# design.net
KiCad netlist of a schematic drawn in Altium Designer
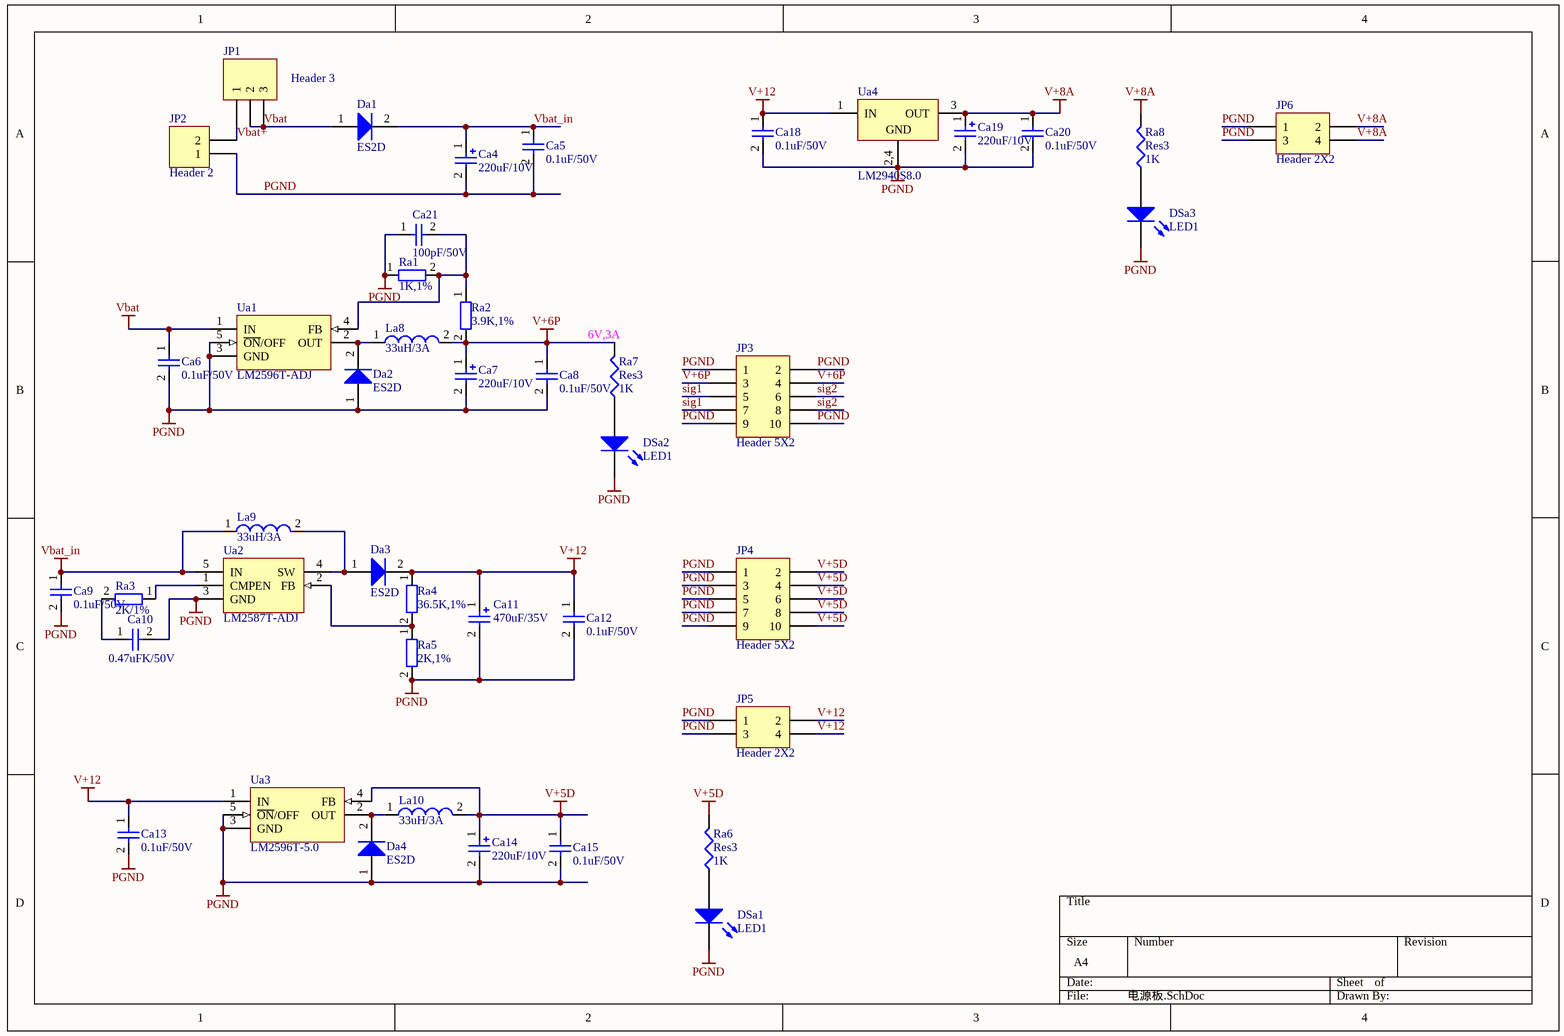
[diagram p0: 电源板.SchDoc]

(export (version "E")
  (design (tool "Eeschema 10.0.6"))
  (components
    (comp (ref "Ca4")
      (value "220uF/10V")
      (footprint "470U")
      (description "Polarized Capacitor (Radial)")
      (fields
        (field (name "MANUFACTURER") "Generic Components")
        (field (name "Comment") "Cap Pol1")
        (field (name "PUBLISHER") "Altium Hobart Technology Centre")
      )
      (libsource (lib "YX002") (part "Cap Pol1"))
    )
    (comp (ref "Ca5")
      (value "0.1uF/50V")
      (footprint "CR2012-0805")
      (description "Capacitor")
      (fields
        (field (name "MANUFACTURER") "Generic Components")
        (field (name "Comment") "Cap")
        (field (name "PUBLISHER") "Altium Hobart Technology Centre")
      )
      (libsource (lib "YX002") (part "Cap"))
    )
    (comp (ref "Ca6")
      (value "0.1uF/50V")
      (footprint "CR2012-0805")
      (description "Capacitor")
      (fields
        (field (name "MANUFACTURER") "Generic Components")
        (field (name "Comment") "Cap")
        (field (name "PUBLISHER") "Altium Hobart Technology Centre")
      )
      (libsource (lib "YX002") (part "Cap"))
    )
    (comp (ref "Ca7")
      (value "220uF/10V")
      (footprint "470U")
      (description "Polarized Capacitor (Radial)")
      (fields
        (field (name "MANUFACTURER") "Generic Components")
        (field (name "Comment") "Cap Pol1")
        (field (name "PUBLISHER") "Altium Hobart Technology Centre")
      )
      (libsource (lib "YX002") (part "Cap Pol1"))
    )
    (comp (ref "Ca8")
      (value "0.1uF/50V")
      (footprint "CR2012-0805")
      (description "Capacitor")
      (fields
        (field (name "MANUFACTURER") "Generic Components")
        (field (name "Comment") "Cap")
        (field (name "PUBLISHER") "Altium Hobart Technology Centre")
      )
      (libsource (lib "YX002") (part "Cap"))
    )
    (comp (ref "Ca9")
      (value "0.1uF/50V")
      (footprint "CR2012-0805")
      (description "Capacitor")
      (fields
        (field (name "MANUFACTURER") "Generic Components")
        (field (name "Comment") "Cap")
        (field (name "PUBLISHER") "Altium Hobart Technology Centre")
      )
      (libsource (lib "YX002") (part "Cap"))
    )
    (comp (ref "Ca10")
      (value "0.47uFK/50V")
      (footprint "CR2012-0805")
      (description "Capacitor")
      (fields
        (field (name "MANUFACTURER") "Generic Components")
        (field (name "Comment") "Cap")
        (field (name "PUBLISHER") "Altium Hobart Technology Centre")
      )
      (libsource (lib "YX002") (part "Cap"))
    )
    (comp (ref "Ca11")
      (value "470uF/35V")
      (footprint "470U")
      (description "Polarized Capacitor (Radial)")
      (fields
        (field (name "MANUFACTURER") "Generic Components")
        (field (name "Comment") "Cap Pol1")
        (field (name "PUBLISHER") "Altium Hobart Technology Centre")
      )
      (libsource (lib "YX002") (part "Cap Pol1"))
    )
    (comp (ref "Ca12")
      (value "0.1uF/50V")
      (footprint "CR2012-0805")
      (description "Capacitor")
      (fields
        (field (name "MANUFACTURER") "Generic Components")
        (field (name "Comment") "Cap")
        (field (name "PUBLISHER") "Altium Hobart Technology Centre")
      )
      (libsource (lib "YX002") (part "Cap"))
    )
    (comp (ref "Ca13")
      (value "0.1uF/50V")
      (footprint "CR2012-0805")
      (description "Capacitor")
      (fields
        (field (name "MANUFACTURER") "Generic Components")
        (field (name "Comment") "Cap")
        (field (name "PUBLISHER") "Altium Hobart Technology Centre")
      )
      (libsource (lib "YX002") (part "Cap"))
    )
    (comp (ref "Ca14")
      (value "220uF/10V")
      (footprint "100u")
      (description "Polarized Capacitor (Radial)")
      (fields
        (field (name "MANUFACTURER") "Generic Components")
        (field (name "Comment") "Cap Pol1")
        (field (name "PUBLISHER") "Altium Hobart Technology Centre")
      )
      (libsource (lib "YX002") (part "Cap Pol1"))
    )
    (comp (ref "Ca15")
      (value "0.1uF/50V")
      (footprint "CR2012-0805")
      (description "Capacitor")
      (fields
        (field (name "MANUFACTURER") "Generic Components")
        (field (name "Comment") "Cap")
        (field (name "PUBLISHER") "Altium Hobart Technology Centre")
      )
      (libsource (lib "YX002") (part "Cap"))
    )
    (comp (ref "Ca18")
      (value "0.1uF/50V")
      (footprint "CR2012-0805")
      (description "Capacitor")
      (fields
        (field (name "MANUFACTURER") "Generic Components")
        (field (name "Comment") "Cap")
        (field (name "PUBLISHER") "Altium Hobart Technology Centre")
      )
      (libsource (lib "YX002") (part "Cap"))
    )
    (comp (ref "Ca19")
      (value "220uF/10V")
      (footprint "100u")
      (description "Polarized Capacitor (Radial)")
      (fields
        (field (name "MANUFACTURER") "Generic Components")
        (field (name "Comment") "Cap Pol1")
        (field (name "PUBLISHER") "Altium Hobart Technology Centre")
      )
      (libsource (lib "YX002") (part "Cap Pol1"))
    )
    (comp (ref "Ca20")
      (value "0.1uF/50V")
      (footprint "CR2012-0805")
      (description "Capacitor")
      (fields
        (field (name "MANUFACTURER") "Generic Components")
        (field (name "Comment") "Cap")
        (field (name "PUBLISHER") "Altium Hobart Technology Centre")
      )
      (libsource (lib "YX002") (part "Cap"))
    )
    (comp (ref "Ca21")
      (value "100pF/50V")
      (footprint "CR2012-0805")
      (description "Capacitor")
      (fields
        (field (name "MANUFACTURER") "Generic Components")
        (field (name "Comment") "Cap")
        (field (name "PUBLISHER") "Altium Hobart Technology Centre")
      )
      (libsource (lib "YX002") (part "Cap"))
    )
    (comp (ref "Da1")
      (value "ES2D")
      (footprint "DO-214-SMB-YX1")
      (description "Ultra-Fast Rectifier Diode")
      (fields
        (field (name "MANUFACTURER") "Generic Components")
        (field (name "Comment") "Diode_UFR")
        (field (name "PUBLISHER") "Altium Hobart Technology Centre")
      )
      (libsource (lib "YX002") (part "Diode_UFR"))
    )
    (comp (ref "Da2")
      (value "ES2D")
      (footprint "DO-214-SMB-YX1")
      (description "Ultra-Fast Rectifier Diode")
      (fields
        (field (name "MANUFACTURER") "Generic Components")
        (field (name "Comment") "Diode_UFR")
        (field (name "PUBLISHER") "Altium Hobart Technology Centre")
      )
      (libsource (lib "YX002") (part "Diode_UFR"))
    )
    (comp (ref "Da3")
      (value "ES2D")
      (footprint "DO-214-SMB-YX1")
      (description "Ultra-Fast Rectifier Diode")
      (fields
        (field (name "MANUFACTURER") "Generic Components")
        (field (name "Comment") "Diode_UFR")
        (field (name "PUBLISHER") "Altium Hobart Technology Centre")
      )
      (libsource (lib "YX002") (part "Diode_UFR"))
    )
    (comp (ref "Da4")
      (value "ES2D")
      (footprint "DO-214-SMB-YX1")
      (description "Ultra-Fast Rectifier Diode")
      (fields
        (field (name "MANUFACTURER") "Generic Components")
        (field (name "Comment") "Diode_UFR")
        (field (name "PUBLISHER") "Altium Hobart Technology Centre")
      )
      (libsource (lib "YX002") (part "Diode_UFR"))
    )
    (comp (ref "DSa1")
      (value "LED1")
      (footprint "CR2012-0805")
      (description "Typical RED GaAs LED")
      (fields (field (name "PUBLISHER") "Altium Limited"))
      (libsource (lib "Miscellaneous Devices") (part "LED1"))
    )
    (comp (ref "DSa2")
      (value "LED1")
      (footprint "CR2012-0805")
      (description "Typical RED GaAs LED")
      (fields (field (name "PUBLISHER") "Altium Limited"))
      (libsource (lib "Miscellaneous Devices") (part "LED1"))
    )
    (comp (ref "DSa3")
      (value "LED1")
      (footprint "CR2012-0805")
      (description "Typical RED GaAs LED")
      (fields (field (name "PUBLISHER") "Altium Limited"))
      (libsource (lib "Miscellaneous Devices") (part "LED1"))
    )
    (comp (ref "JP1")
      (value "Header 3")
      (footprint "KG_3")
      (description "Header, 3-Pin")
      (fields (field (name "PUBLISHER") "Altium Limited"))
      (libsource (lib "Miscellaneous Connectors") (part "Header 3"))
    )
    (comp (ref "JP2")
      (value "Header 2")
      (footprint "CON_X2_B")
      (description "Header, 2-Pin")
      (fields (field (name "PUBLISHER") "Altium Limited"))
      (libsource (lib "Miscellaneous Connectors") (part "Header 2"))
    )
    (comp (ref "JP3")
      (value "Header 5X2")
      (footprint "HDR2X5")
      (description "Header, 5-Pin, Dual row")
      (fields (field (name "PUBLISHER") "Altium Limited"))
      (libsource (lib "Miscellaneous Connectors") (part "Header 5X2"))
    )
    (comp (ref "JP4")
      (value "Header 5X2")
      (footprint "HDR2X5")
      (description "Header, 5-Pin, Dual row")
      (fields (field (name "PUBLISHER") "Altium Limited"))
      (libsource (lib "Miscellaneous Connectors") (part "Header 5X2"))
    )
    (comp (ref "JP5")
      (value "Header 2X2")
      (footprint "HDR2X2")
      (description "Header, 2-Pin, Dual row")
      (fields (field (name "PUBLISHER") "Altium Limited"))
      (libsource (lib "Miscellaneous Connectors") (part "Header 2X2"))
    )
    (comp (ref "JP6")
      (value "Header 2X2")
      (footprint "HDR2X2")
      (description "Header, 2-Pin, Dual row")
      (fields (field (name "PUBLISHER") "Altium Limited"))
      (libsource (lib "Miscellaneous Connectors") (part "Header 2X2"))
    )
    (comp (ref "La8")
      (value "33uH/3A")
      (footprint "INDUCTOR-YX14")
      (description "Inductor")
      (fields
        (field (name "MANUFACTURER") "Generic Components")
        (field (name "PUBLISHER") "Altium Hobart Technology Centre")
      )
      (libsource (lib "YX002") (part "Inductor"))
    )
    (comp (ref "La9")
      (value "33uH/3A")
      (footprint "INDUCTOR-YX14")
      (description "Inductor")
      (fields
        (field (name "MANUFACTURER") "Generic Components")
        (field (name "PUBLISHER") "Altium Hobart Technology Centre")
      )
      (libsource (lib "YX002") (part "Inductor"))
    )
    (comp (ref "La10")
      (value "33uH/3A")
      (footprint "INDUCTOR-YX14")
      (description "Inductor")
      (fields
        (field (name "MANUFACTURER") "Generic Components")
        (field (name "PUBLISHER") "Altium Hobart Technology Centre")
      )
      (libsource (lib "YX002") (part "Inductor"))
    )
    (comp (ref "Ra1")
      (value "1K,1%")
      (footprint "CR2012-0805")
      (description "Resistor")
      (fields
        (field (name "MANUFACTURER") "Generic Components")
        (field (name "Comment") "Res2")
        (field (name "PUBLISHER") "Altium Hobart Technology Centre")
      )
      (libsource (lib "YX002") (part "Res2"))
    )
    (comp (ref "Ra2")
      (value "3.9K,1%")
      (footprint "CR2012-0805")
      (description "Resistor")
      (fields
        (field (name "MANUFACTURER") "Generic Components")
        (field (name "Comment") "Res2")
        (field (name "PUBLISHER") "Altium Hobart Technology Centre")
      )
      (libsource (lib "") (part "Res2_2"))
    )
    (comp (ref "Ra3")
      (value "2K/1%")
      (footprint "CR2012-0805")
      (description "Resistor")
      (fields
        (field (name "MANUFACTURER") "Generic Components")
        (field (name "Comment") "Res2")
        (field (name "PUBLISHER") "Altium Hobart Technology Centre")
      )
      (libsource (lib "") (part "Res2_1"))
    )
    (comp (ref "Ra4")
      (value "36.5K,1%")
      (footprint "CR2012-0805")
      (description "Resistor")
      (fields
        (field (name "MANUFACTURER") "Generic Components")
        (field (name "Comment") "Res2")
        (field (name "PUBLISHER") "Altium Hobart Technology Centre")
      )
      (libsource (lib "") (part "Res2_2"))
    )
    (comp (ref "Ra5")
      (value "2K,1%")
      (footprint "CR2012-0805")
      (description "Resistor")
      (fields
        (field (name "MANUFACTURER") "Generic Components")
        (field (name "Comment") "Res2")
        (field (name "PUBLISHER") "Altium Hobart Technology Centre")
      )
      (libsource (lib "") (part "Res2_2"))
    )
    (comp (ref "Ra6")
      (value "Res3")
      (footprint "CR2012-0805")
      (description "Resistor")
      (fields (field (name "ALTIUM_VALUE") "1K") (field (name "PUBLISHER") "Altium Limited"))
      (libsource (lib "Miscellaneous Devices") (part "Res3"))
    )
    (comp (ref "Ra7")
      (value "Res3")
      (footprint "CR2012-0805")
      (description "Resistor")
      (fields (field (name "ALTIUM_VALUE") "1K") (field (name "PUBLISHER") "Altium Limited"))
      (libsource (lib "Miscellaneous Devices") (part "Res3"))
    )
    (comp (ref "Ra8")
      (value "Res3")
      (footprint "CR2012-0805")
      (description "Resistor")
      (fields (field (name "ALTIUM_VALUE") "1K") (field (name "PUBLISHER") "Altium Limited"))
      (libsource (lib "Miscellaneous Devices") (part "Res3"))
    )
    (comp (ref "Ua1")
      (value "LM2596T-ADJ")
      (footprint "LM2596")
      (description "Simple Switcher Power Converter 150 kHz 3A Step Down Voltage Regulator")
      (fields (field (name "PUBLISHER") "Altium Limited"))
      (libsource (lib "NSC Power Mgt Switching Regulator") (part "LM2596T-5.0"))
    )
    (comp (ref "Ua2")
      (value "LM2587T-ADJ")
      (footprint "LM2596")
      (description "Simple Switcher 5A Flyback Regulator")
      (fields (field (name "PUBLISHER") "Altium Limited"))
      (libsource (lib "NSC Power Mgt Switching Regulator") (part "LM2587T-ADJ"))
    )
    (comp (ref "Ua3")
      (value "LM2596T-5.0")
      (footprint "LM2596")
      (description "Simple Switcher Power Converter 150 kHz 3A Step Down Voltage Regulator")
      (fields (field (name "PUBLISHER") "Altium Limited"))
      (libsource (lib "NSC Power Mgt Switching Regulator") (part "LM2596T-5.0"))
    )
    (comp (ref "Ua4")
      (value "LM2940S8.0")
      (footprint "SOT-223")
      (description "1A Low-Dropout Regulator")
      (fields (field (name "PUBLISHER") "Altium Limited"))
      (libsource (lib "NSC Power Mgt Voltage Regulator") (part "LM2940S8.0"))
    )
  )
  (nets
    (net (code "1") (name "/Vbat+") (class "Default")
      (node (ref "JP1") (pin "1") (pinfunction "1_1") (pintype "passive"))
      (node (ref "JP2") (pin "2") (pinfunction "2_2") (pintype "passive"))
    )
    (net (code "2") (name "/sig1") (class "Default")
      (node (ref "JP3") (pin "5") (pinfunction "5_5") (pintype "passive"))
      (node (ref "JP3") (pin "7") (pinfunction "7_7") (pintype "passive"))
    )
    (net (code "3") (name "/sig2") (class "Default")
      (node (ref "JP3") (pin "6") (pinfunction "6_6") (pintype "passive"))
      (node (ref "JP3") (pin "8") (pinfunction "8_8") (pintype "passive"))
    )
    (net (code "4") (name "Net-(Ca10-Pad1)") (class "Default")
      (node (ref "Ca10") (pin "1") (pinfunction "1_1") (pintype "passive"))
      (node (ref "Ra3") (pin "2") (pinfunction "2_2") (pintype "passive"))
    )
    (net (code "5") (name "Net-(DSa1-A)") (class "Default")
      (node (ref "DSa1") (pin "1") (pinfunction "A_1") (pintype "passive"))
      (node (ref "Ra6") (pin "1") (pinfunction "1_1") (pintype "passive"))
    )
    (net (code "6") (name "Net-(DSa2-A)") (class "Default")
      (node (ref "DSa2") (pin "1") (pinfunction "A_1") (pintype "passive"))
      (node (ref "Ra7") (pin "1") (pinfunction "1_1") (pintype "passive"))
    )
    (net (code "7") (name "Net-(DSa3-A)") (class "Default")
      (node (ref "DSa3") (pin "1") (pinfunction "A_1") (pintype "passive"))
      (node (ref "Ra8") (pin "1") (pinfunction "1_1") (pintype "passive"))
    )
    (net (code "8") (name "Net-(Da2-K)") (class "Default")
      (node (ref "Da2") (pin "2") (pinfunction "K_2") (pintype "passive"))
      (node (ref "La8") (pin "1") (pinfunction "1_1") (pintype "passive"))
      (node (ref "Ua1") (pin "2") (pinfunction "OUT_2") (pintype "power_in"))
    )
    (net (code "9") (name "Net-(Da3-A)") (class "Default")
      (node (ref "Da3") (pin "1") (pinfunction "A_1") (pintype "passive"))
      (node (ref "La9") (pin "2") (pinfunction "2_2") (pintype "passive"))
      (node (ref "Ua2") (pin "4") (pinfunction "SW_4") (pintype "power_in"))
    )
    (net (code "10") (name "Net-(Da4-K)") (class "Default")
      (node (ref "Da4") (pin "2") (pinfunction "K_2") (pintype "passive"))
      (node (ref "La10") (pin "1") (pinfunction "1_1") (pintype "passive"))
      (node (ref "Ua3") (pin "2") (pinfunction "OUT_2") (pintype "power_in"))
    )
    (net (code "11") (name "Net-(Ua1-FB)") (class "Default")
      (node (ref "Ca21") (pin "2") (pinfunction "2_2") (pintype "passive"))
      (node (ref "Ra1") (pin "2") (pinfunction "2_2") (pintype "passive"))
      (node (ref "Ra2") (pin "1") (pinfunction "1_1") (pintype "passive"))
      (node (ref "Ua1") (pin "4") (pinfunction "FB_4") (pintype "input"))
    )
    (net (code "12") (name "Net-(Ua2-CMPEN)") (class "Default")
      (node (ref "Ra3") (pin "1") (pinfunction "1_1") (pintype "passive"))
      (node (ref "Ua2") (pin "1") (pinfunction "CMPEN_1") (pintype "passive"))
    )
    (net (code "13") (name "Net-(Ua2-FB)") (class "Default")
      (node (ref "Ra4") (pin "2") (pinfunction "2_2") (pintype "passive"))
      (node (ref "Ra5") (pin "1") (pinfunction "1_1") (pintype "passive"))
      (node (ref "Ua2") (pin "2") (pinfunction "FB_2") (pintype "input"))
    )
    (net (code "14") (name "PGND") (class "Default")
      (node (ref "Ca10") (pin "2") (pinfunction "2_2") (pintype "passive"))
      (node (ref "Ca11") (pin "2") (pinfunction "2_2") (pintype "passive"))
      (node (ref "Ca12") (pin "2") (pinfunction "2_2") (pintype "passive"))
      (node (ref "Ca13") (pin "2") (pinfunction "2_2") (pintype "passive"))
      (node (ref "Ca14") (pin "2") (pinfunction "2_2") (pintype "passive"))
      (node (ref "Ca15") (pin "2") (pinfunction "2_2") (pintype "passive"))
      (node (ref "Ca18") (pin "2") (pinfunction "2_2") (pintype "passive"))
      (node (ref "Ca19") (pin "2") (pinfunction "2_2") (pintype "passive"))
      (node (ref "Ca20") (pin "2") (pinfunction "2_2") (pintype "passive"))
      (node (ref "Ca21") (pin "1") (pinfunction "1_1") (pintype "passive"))
      (node (ref "Ca4") (pin "2") (pinfunction "2_2") (pintype "passive"))
      (node (ref "Ca5") (pin "2") (pinfunction "2_2") (pintype "passive"))
      (node (ref "Ca6") (pin "2") (pinfunction "2_2") (pintype "passive"))
      (node (ref "Ca7") (pin "2") (pinfunction "2_2") (pintype "passive"))
      (node (ref "Ca8") (pin "2") (pinfunction "2_2") (pintype "passive"))
      (node (ref "Ca9") (pin "2") (pinfunction "2_2") (pintype "passive"))
      (node (ref "DSa1") (pin "2") (pinfunction "K_2") (pintype "passive"))
      (node (ref "DSa2") (pin "2") (pinfunction "K_2") (pintype "passive"))
      (node (ref "DSa3") (pin "2") (pinfunction "K_2") (pintype "passive"))
      (node (ref "Da2") (pin "1") (pinfunction "A_1") (pintype "passive"))
      (node (ref "Da4") (pin "1") (pinfunction "A_1") (pintype "passive"))
      (node (ref "JP2") (pin "1") (pinfunction "1_1") (pintype "passive"))
      (node (ref "JP3") (pin "1") (pinfunction "1_1") (pintype "passive"))
      (node (ref "JP3") (pin "10") (pinfunction "10_10") (pintype "passive"))
      (node (ref "JP3") (pin "2") (pinfunction "2_2") (pintype "passive"))
      (node (ref "JP3") (pin "9") (pinfunction "9_9") (pintype "passive"))
      (node (ref "JP4") (pin "1") (pinfunction "1_1") (pintype "passive"))
      (node (ref "JP4") (pin "3") (pinfunction "3_3") (pintype "passive"))
      (node (ref "JP4") (pin "5") (pinfunction "5_5") (pintype "passive"))
      (node (ref "JP4") (pin "7") (pinfunction "7_7") (pintype "passive"))
      (node (ref "JP4") (pin "9") (pinfunction "9_9") (pintype "passive"))
      (node (ref "JP5") (pin "1") (pinfunction "1_1") (pintype "passive"))
      (node (ref "JP5") (pin "3") (pinfunction "3_3") (pintype "passive"))
      (node (ref "JP6") (pin "1") (pinfunction "1_1") (pintype "passive"))
      (node (ref "JP6") (pin "3") (pinfunction "3_3") (pintype "passive"))
      (node (ref "Ra1") (pin "1") (pinfunction "1_1") (pintype "passive"))
      (node (ref "Ra5") (pin "2") (pinfunction "2_2") (pintype "passive"))
      (node (ref "Ua1") (pin "3") (pinfunction "GND_3") (pintype "power_in"))
      (node (ref "Ua1") (pin "5") (pinfunction "~{ON}/OFF_5") (pintype "input"))
      (node (ref "Ua2") (pin "3") (pinfunction "GND_3") (pintype "power_in"))
      (node (ref "Ua3") (pin "3") (pinfunction "GND_3") (pintype "power_in"))
      (node (ref "Ua3") (pin "5") (pinfunction "~{ON}/OFF_5") (pintype "input"))
      (node (ref "Ua4") (pin "2") (pinfunction "GND_2") (pintype "power_in"))
      (node (ref "Ua4") (pin "4") (pinfunction "GND_4") (pintype "power_in"))
    )
    (net (code "15") (name "V+5D") (class "Default")
      (node (ref "Ca14") (pin "1") (pinfunction "1_1") (pintype "passive"))
      (node (ref "Ca15") (pin "1") (pinfunction "1_1") (pintype "passive"))
      (node (ref "JP4") (pin "10") (pinfunction "10_10") (pintype "passive"))
      (node (ref "JP4") (pin "2") (pinfunction "2_2") (pintype "passive"))
      (node (ref "JP4") (pin "4") (pinfunction "4_4") (pintype "passive"))
      (node (ref "JP4") (pin "6") (pinfunction "6_6") (pintype "passive"))
      (node (ref "JP4") (pin "8") (pinfunction "8_8") (pintype "passive"))
      (node (ref "La10") (pin "2") (pinfunction "2_2") (pintype "passive"))
      (node (ref "Ra6") (pin "2") (pinfunction "2_2") (pintype "passive"))
      (node (ref "Ua3") (pin "4") (pinfunction "FB_4") (pintype "input"))
    )
    (net (code "16") (name "V+6P") (class "Default")
      (node (ref "Ca7") (pin "1") (pinfunction "1_1") (pintype "passive"))
      (node (ref "Ca8") (pin "1") (pinfunction "1_1") (pintype "passive"))
      (node (ref "JP3") (pin "3") (pinfunction "3_3") (pintype "passive"))
      (node (ref "JP3") (pin "4") (pinfunction "4_4") (pintype "passive"))
      (node (ref "La8") (pin "2") (pinfunction "2_2") (pintype "passive"))
      (node (ref "Ra2") (pin "2") (pinfunction "2_2") (pintype "passive"))
      (node (ref "Ra7") (pin "2") (pinfunction "2_2") (pintype "passive"))
    )
    (net (code "17") (name "V+8A") (class "Default")
      (node (ref "Ca19") (pin "1") (pinfunction "1_1") (pintype "passive"))
      (node (ref "Ca20") (pin "1") (pinfunction "1_1") (pintype "passive"))
      (node (ref "JP6") (pin "2") (pinfunction "2_2") (pintype "passive"))
      (node (ref "JP6") (pin "4") (pinfunction "4_4") (pintype "passive"))
      (node (ref "Ra8") (pin "2") (pinfunction "2_2") (pintype "passive"))
      (node (ref "Ua4") (pin "3") (pinfunction "OUT_3") (pintype "power_in"))
    )
    (net (code "18") (name "V+12") (class "Default")
      (node (ref "Ca11") (pin "1") (pinfunction "1_1") (pintype "passive"))
      (node (ref "Ca12") (pin "1") (pinfunction "1_1") (pintype "passive"))
      (node (ref "Ca13") (pin "1") (pinfunction "1_1") (pintype "passive"))
      (node (ref "Ca18") (pin "1") (pinfunction "1_1") (pintype "passive"))
      (node (ref "Da3") (pin "2") (pinfunction "K_2") (pintype "passive"))
      (node (ref "JP5") (pin "2") (pinfunction "2_2") (pintype "passive"))
      (node (ref "JP5") (pin "4") (pinfunction "4_4") (pintype "passive"))
      (node (ref "Ra4") (pin "1") (pinfunction "1_1") (pintype "passive"))
      (node (ref "Ua3") (pin "1") (pinfunction "IN_1") (pintype "power_in"))
      (node (ref "Ua4") (pin "1") (pinfunction "IN_1") (pintype "power_in"))
    )
    (net (code "19") (name "Vbat") (class "Default")
      (node (ref "Ca6") (pin "1") (pinfunction "1_1") (pintype "passive"))
      (node (ref "Da1") (pin "1") (pinfunction "A_1") (pintype "passive"))
      (node (ref "JP1") (pin "2") (pinfunction "2_2") (pintype "passive"))
      (node (ref "JP1") (pin "3") (pinfunction "3_3") (pintype "passive"))
      (node (ref "Ua1") (pin "1") (pinfunction "IN_1") (pintype "power_in"))
    )
    (net (code "20") (name "Vbat_in") (class "Default")
      (node (ref "Ca4") (pin "1") (pinfunction "1_1") (pintype "passive"))
      (node (ref "Ca5") (pin "1") (pinfunction "1_1") (pintype "passive"))
      (node (ref "Ca9") (pin "1") (pinfunction "1_1") (pintype "passive"))
      (node (ref "Da1") (pin "2") (pinfunction "K_2") (pintype "passive"))
      (node (ref "La9") (pin "1") (pinfunction "1_1") (pintype "passive"))
      (node (ref "Ua2") (pin "5") (pinfunction "IN_5") (pintype "power_in"))
    )
  )
)
